# distortion.net
KiCad netlist of a schematic drawn in EAGLE
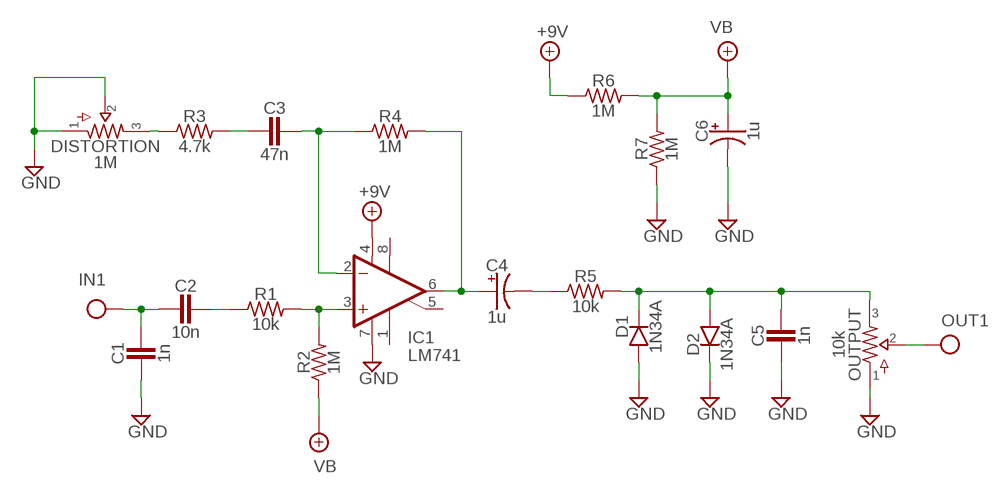
[diagram p0: schematic, sheet 1]

(export (version "E")
  (design (tool "Eeschema 10.0.6"))
  (components
    (comp (ref "C1")
      (value "1n")
      (footprint "eagle-import:BOX_SMALL")
      (libsource (lib "eagle-import") (part "CER/FILMBOX.1"))
    )
    (comp (ref "C2")
      (value "10n")
      (footprint "eagle-import:BOX_SMALL")
      (libsource (lib "eagle-import") (part "CER/FILMBOX.1"))
    )
    (comp (ref "C3")
      (value "47n")
      (footprint "eagle-import:BOX_SMALL")
      (libsource (lib "eagle-import") (part "CER/FILMBOX.1"))
    )
    (comp (ref "C4")
      (value "1u")
      (footprint "eagle-import:050_020")
      (libsource (lib "eagle-import") (part "0500"))
    )
    (comp (ref "C5")
      (value "1n")
      (footprint "eagle-import:BOX_SMALL")
      (libsource (lib "eagle-import") (part "CER/FILMBOX.1"))
    )
    (comp (ref "C6")
      (value "1u")
      (footprint "eagle-import:050_020")
      (libsource (lib "eagle-import") (part "0500"))
    )
    (comp (ref "D1")
      (value "1N34A")
      (footprint "eagle-import:DO41-2")
      (libsource (lib "eagle-import") (part "DO41.2"))
    )
    (comp (ref "D2")
      (value "1N34A")
      (footprint "eagle-import:DO41-2")
      (libsource (lib "eagle-import") (part "DO41.2"))
    )
    (comp (ref "DISTORTION")
      (value "1M")
      (footprint "eagle-import:16MM")
      (libsource (lib "eagle-import") (part "POTS16MM"))
    )
    (comp (ref "IC1")
      (value "LM741")
      (footprint "eagle-import:DIL0")
      (libsource (lib "eagle-import") (part "SINGLETH"))
    )
    (comp (ref "IN1")
      (value "IN(T)")
      (footprint "eagle-import:SQUARE")
      (libsource (lib "eagle-import") (part "IN(T)"))
    )
    (comp (ref "OUTPUT")
      (value "10k")
      (footprint "eagle-import:16MM")
      (libsource (lib "eagle-import") (part "POTS16MM"))
    )
    (comp (ref "R1")
      (value "10k")
      (footprint "eagle-import:R0207_3")
      (libsource (lib "eagle-import") (part "R_.3B"))
    )
    (comp (ref "R2")
      (value "1M")
      (footprint "eagle-import:R0207_3")
      (libsource (lib "eagle-import") (part "R_.3B"))
    )
    (comp (ref "R3")
      (value "4.7k")
      (footprint "eagle-import:R0207_3")
      (libsource (lib "eagle-import") (part "R_.3B"))
    )
    (comp (ref "R4")
      (value "1M")
      (footprint "eagle-import:R0207_3")
      (libsource (lib "eagle-import") (part "R_.3B"))
    )
    (comp (ref "R5")
      (value "10k")
      (footprint "eagle-import:R0207_3")
      (libsource (lib "eagle-import") (part "R_.3B"))
    )
    (comp (ref "R6")
      (value "1M")
      (footprint "eagle-import:R0207_3")
      (libsource (lib "eagle-import") (part "R_.3B"))
    )
    (comp (ref "R7")
      (value "1M")
      (footprint "eagle-import:R0207_3")
      (libsource (lib "eagle-import") (part "R_.3B"))
    )
  )
  (nets
    (net (code "1") (name "+9V") (class "Default")
      (node (ref "IC1") (pin "4") (pinfunction "V-_4") (pintype "power_in"))
      (node (ref "R6") (pin "1") (pinfunction "1_1") (pintype "passive"))
    )
    (net (code "2") (name "GND") (class "Default")
      (node (ref "C1") (pin "2") (pinfunction "2_2") (pintype "passive"))
      (node (ref "C5") (pin "2") (pinfunction "2_2") (pintype "passive"))
      (node (ref "C6") (pin "-") (pinfunction "-_-") (pintype "passive"))
      (node (ref "D1") (pin "A") (pinfunction "A_A") (pintype "passive"))
      (node (ref "D2") (pin "C") (pinfunction "C_C") (pintype "passive"))
      (node (ref "DISTORTION") (pin "1") (pinfunction "1_1") (pintype "passive"))
      (node (ref "DISTORTION") (pin "2") (pinfunction "2_2") (pintype "passive"))
      (node (ref "IC1") (pin "7") (pinfunction "V+_7") (pintype "power_in"))
      (node (ref "OUTPUT") (pin "1") (pinfunction "1_1") (pintype "passive"))
      (node (ref "R7") (pin "1") (pinfunction "1_1") (pintype "passive"))
    )
    (net (code "3") (name "IN(T)") (class "Default")
      (node (ref "C1") (pin "1") (pinfunction "1_1") (pintype "passive"))
      (node (ref "C2") (pin "2") (pinfunction "2_2") (pintype "passive"))
      (node (ref "IN1") (pin "1") (pinfunction "IN_1") (pintype "power_in"))
    )
    (net (code "4") (name "Net-(C2-Pad1)") (class "Default")
      (node (ref "C2") (pin "1") (pinfunction "1_1") (pintype "passive"))
      (node (ref "R1") (pin "1") (pinfunction "1_1") (pintype "passive"))
    )
    (net (code "5") (name "Net-(C3-Pad2)") (class "Default")
      (node (ref "C3") (pin "2") (pinfunction "2_2") (pintype "passive"))
      (node (ref "R3") (pin "2") (pinfunction "2_2") (pintype "passive"))
    )
    (net (code "6") (name "Net-(C4-Pad-)") (class "Default")
      (node (ref "C4") (pin "-") (pinfunction "-_-") (pintype "passive"))
      (node (ref "R5") (pin "1") (pinfunction "1_1") (pintype "passive"))
    )
    (net (code "7") (name "Net-(C5-Pad1)") (class "Default")
      (node (ref "C5") (pin "1") (pinfunction "1_1") (pintype "passive"))
      (node (ref "D1") (pin "C") (pinfunction "C_C") (pintype "passive"))
      (node (ref "D2") (pin "A") (pinfunction "A_A") (pintype "passive"))
      (node (ref "OUTPUT") (pin "3") (pinfunction "3_3") (pintype "passive"))
      (node (ref "R5") (pin "2") (pinfunction "2_2") (pintype "passive"))
    )
    (net (code "8") (name "Net-(DISTORTION-Pad3)") (class "Default")
      (node (ref "DISTORTION") (pin "3") (pinfunction "3_3") (pintype "passive"))
      (node (ref "R3") (pin "1") (pinfunction "1_1") (pintype "passive"))
    )
    (net (code "9") (name "Net-(IC1-+IN)") (class "Default")
      (node (ref "IC1") (pin "3") (pinfunction "+IN_3") (pintype "input"))
      (node (ref "R1") (pin "2") (pinfunction "2_2") (pintype "passive"))
      (node (ref "R2") (pin "2") (pinfunction "2_2") (pintype "passive"))
    )
    (net (code "10") (name "Net-(IC1--IN)") (class "Default")
      (node (ref "C3") (pin "1") (pinfunction "1_1") (pintype "passive"))
      (node (ref "IC1") (pin "2") (pinfunction "-IN_2") (pintype "input"))
      (node (ref "R4") (pin "1") (pinfunction "1_1") (pintype "passive"))
    )
    (net (code "11") (name "Net-(IC1-OUT)") (class "Default")
      (node (ref "C4") (pin "+") (pinfunction "+_+") (pintype "passive"))
      (node (ref "IC1") (pin "6") (pinfunction "OUT_6") (pintype "output"))
      (node (ref "R4") (pin "2") (pinfunction "2_2") (pintype "passive"))
    )
    (net (code "12") (name "OUT") (class "Default")
      (node (ref "OUTPUT") (pin "2") (pinfunction "2_2") (pintype "passive"))
    )
    (net (code "13") (name "VB") (class "Default")
      (node (ref "C6") (pin "+") (pinfunction "+_+") (pintype "passive"))
      (node (ref "R2") (pin "1") (pinfunction "1_1") (pintype "passive"))
      (node (ref "R6") (pin "2") (pinfunction "2_2") (pintype "passive"))
      (node (ref "R7") (pin "2") (pinfunction "2_2") (pintype "passive"))
    )
    (net (code "14") (name "unconnected-(IC1-ON1-Pad1)") (class "Default")
      (node (ref "IC1") (pin "1") (pinfunction "ON1_1") (pintype "passive"))
    )
    (net (code "15") (name "unconnected-(IC1-ON2-Pad5)") (class "Default")
      (node (ref "IC1") (pin "5") (pinfunction "ON2_5") (pintype "passive"))
    )
    (net (code "16") (name "unconnected-(IC1-OPT-Pad8)") (class "Default")
      (node (ref "IC1") (pin "8") (pinfunction "OPT_8") (pintype "passive"))
    )
  )
)
